# ziffy_board_v6.net
KiCad netlist of a schematic drawn in EAGLE
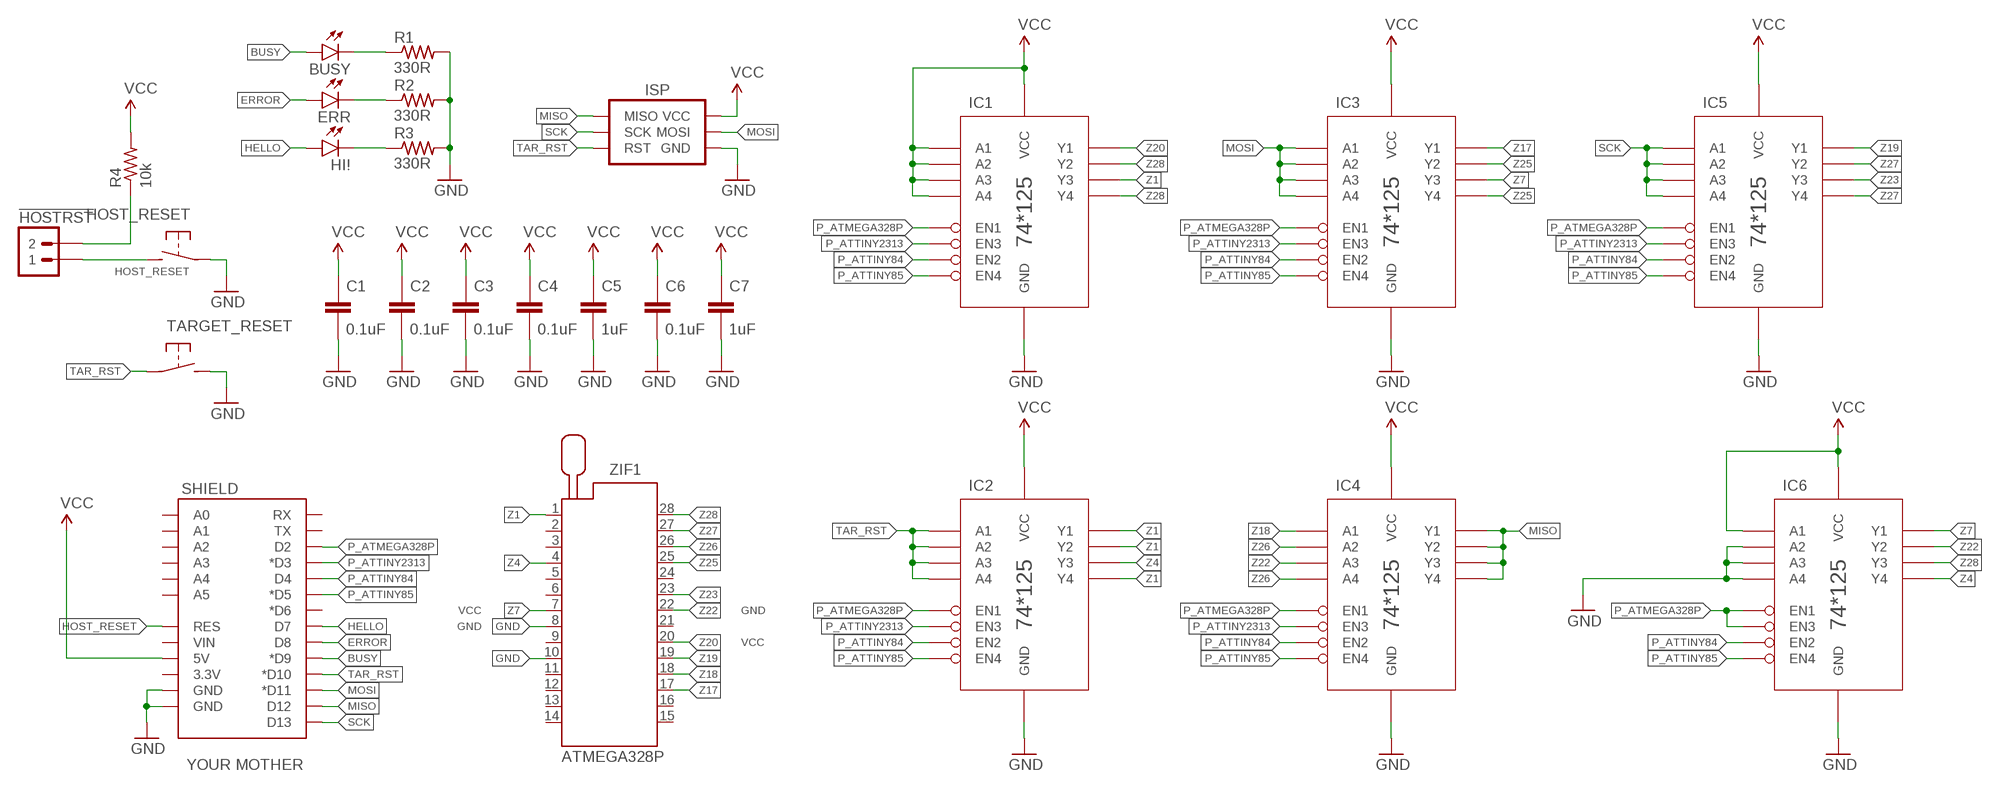
[diagram p0: schematic, sheet 1]

(export (version "E")
  (design (tool "Eeschema 10.0.6"))
  (components
    (comp (ref "!HOSTRST")
      (value "M02PTH")
      (footprint "eagle-import:1X02")
      (libsource (lib "eagle-import") (part "M02PTH"))
    )
    (comp (ref "BUSY")
      (value "YELLOW")
      (footprint "eagle-import:LED3MM")
      (libsource (lib "eagle-import") (part "LED3MM"))
    )
    (comp (ref "C1")
      (value "0.1uF")
      (footprint "eagle-import:C025-024X044")
      (libsource (lib "eagle-import") (part "CAPACITOR-CERAMIC025-024X044"))
    )
    (comp (ref "C2")
      (value "0.1uF")
      (footprint "eagle-import:C025-024X044")
      (libsource (lib "eagle-import") (part "CAPACITOR-CERAMIC025-024X044"))
    )
    (comp (ref "C3")
      (value "0.1uF")
      (footprint "eagle-import:C025-024X044")
      (libsource (lib "eagle-import") (part "CAPACITOR-CERAMIC025-024X044"))
    )
    (comp (ref "C4")
      (value "0.1uF")
      (footprint "eagle-import:C025-024X044")
      (libsource (lib "eagle-import") (part "CAPACITOR-CERAMIC025-024X044"))
    )
    (comp (ref "C5")
      (value "1uF")
      (footprint "eagle-import:C025-024X044")
      (libsource (lib "eagle-import") (part "CAPACITOR-CERAMIC025-024X044"))
    )
    (comp (ref "C6")
      (value "0.1uF")
      (footprint "eagle-import:C025-024X044")
      (libsource (lib "eagle-import") (part "CAPACITOR-CERAMIC025-024X044"))
    )
    (comp (ref "C7")
      (value "1uF")
      (footprint "eagle-import:C025-024X044")
      (libsource (lib "eagle-import") (part "CAPACITOR-CERAMIC025-024X044"))
    )
    (comp (ref "ERR")
      (value "RED")
      (footprint "eagle-import:LED3MM")
      (libsource (lib "eagle-import") (part "LED3MM"))
    )
    (comp (ref "HI!")
      (value "GREEN")
      (footprint "eagle-import:LED3MM")
      (libsource (lib "eagle-import") (part "LED3MM"))
    )
    (comp (ref "HOST_RESET")
      (value "SPST-NO-TACT6MM-PTH-SMALL-PADS")
      (footprint "eagle-import:DTS-6-SMALL-PADS")
      (libsource (lib "eagle-import") (part "SPST-NO-TACT6MM-PTH-SMALL-PADS"))
    )
    (comp (ref "IC1")
      (value "74HC125")
      (footprint "eagle-import:SO14")
      (libsource (lib "eagle-import") (part "74125SOIC14"))
    )
    (comp (ref "IC2")
      (value "74HC125")
      (footprint "eagle-import:SO14")
      (libsource (lib "eagle-import") (part "74125SOIC14"))
    )
    (comp (ref "IC3")
      (value "74HC125")
      (footprint "eagle-import:SO14")
      (libsource (lib "eagle-import") (part "74125SOIC14"))
    )
    (comp (ref "IC4")
      (value "74HC125")
      (footprint "eagle-import:SO14")
      (libsource (lib "eagle-import") (part "74125SOIC14"))
    )
    (comp (ref "IC5")
      (value "74HC125")
      (footprint "eagle-import:SO14")
      (libsource (lib "eagle-import") (part "74125SOIC14"))
    )
    (comp (ref "IC6")
      (value "74HC125")
      (footprint "eagle-import:SO14")
      (libsource (lib "eagle-import") (part "74125SOIC14"))
    )
    (comp (ref "ISP")
      (value "AVR_SPI_PRG_6PTH-SHROUD")
      (footprint "eagle-import:2X3-SHROUDED")
      (libsource (lib "eagle-import") (part "AVR_SPI_PRG_6PTH-SHROUD"))
    )
    (comp (ref "R1")
      (value "330R")
      (footprint "eagle-import:RESISTOR-AXIAL-PTH-5.08MM")
      (libsource (lib "eagle-import") (part "RESISTORPTH-AXIAL-5.08MM"))
    )
    (comp (ref "R2")
      (value "330R")
      (footprint "eagle-import:RESISTOR-AXIAL-PTH-5.08MM")
      (libsource (lib "eagle-import") (part "RESISTORPTH-AXIAL-5.08MM"))
    )
    (comp (ref "R3")
      (value "330R")
      (footprint "eagle-import:RESISTOR-AXIAL-PTH-5.08MM")
      (libsource (lib "eagle-import") (part "RESISTORPTH-AXIAL-5.08MM"))
    )
    (comp (ref "R4")
      (value "10k")
      (footprint "eagle-import:RESISTOR-AXIAL-PTH-5.08MM")
      (libsource (lib "eagle-import") (part "RESISTORPTH-AXIAL-5.08MM"))
    )
    (comp (ref "SHIELD")
      (value "YOUR MOTHER")
      (footprint "eagle-import:ARDUINO_SHIELD_NOOUTLINE_INSIDE_SMALLER")
      (libsource (lib "eagle-import") (part "ARDUINO_SHIELD_SMALLER"))
    )
    (comp (ref "TARGET_RESET")
      (value "SPST-NO-TACT6MM-PTH-SMALL-PADS")
      (footprint "eagle-import:DTS-6-SMALL-PADS")
      (libsource (lib "eagle-import") (part "SPST-NO-TACT6MM-PTH-SMALL-PADS"))
    )
    (comp (ref "ZIF1")
      (value "ATMEGA328P")
      (footprint "eagle-import:ZIF28")
      (libsource (lib "eagle-import") (part "ZIF28"))
    )
  )
  (nets
    (net (code "1") (name "BUSY") (class "Default")
      (node (ref "BUSY") (pin "A") (pinfunction "A_A") (pintype "passive"))
      (node (ref "SHIELD") (pin "D9") (pinfunction "*D9_D9") (pintype "bidirectional"))
    )
    (net (code "2") (name "ERROR") (class "Default")
      (node (ref "ERR") (pin "A") (pinfunction "A_A") (pintype "passive"))
      (node (ref "SHIELD") (pin "D8") (pinfunction "D8_D8") (pintype "bidirectional"))
    )
    (net (code "3") (name "GND") (class "Default")
      (node (ref "C1") (pin "2") (pinfunction "2_2") (pintype "passive"))
      (node (ref "C2") (pin "2") (pinfunction "2_2") (pintype "passive"))
      (node (ref "C3") (pin "2") (pinfunction "2_2") (pintype "passive"))
      (node (ref "C4") (pin "2") (pinfunction "2_2") (pintype "passive"))
      (node (ref "C5") (pin "2") (pinfunction "2_2") (pintype "passive"))
      (node (ref "C6") (pin "2") (pinfunction "2_2") (pintype "passive"))
      (node (ref "C7") (pin "2") (pinfunction "2_2") (pintype "passive"))
      (node (ref "HOST_RESET") (pin "1") (pinfunction "1_1") (pintype "passive"))
      (node (ref "HOST_RESET") (pin "2") (pinfunction "1_2") (pintype "passive"))
      (node (ref "IC1") (pin "7") (pinfunction "GND_7") (pintype "bidirectional"))
      (node (ref "IC2") (pin "7") (pinfunction "GND_7") (pintype "bidirectional"))
      (node (ref "IC3") (pin "7") (pinfunction "GND_7") (pintype "bidirectional"))
      (node (ref "IC4") (pin "7") (pinfunction "GND_7") (pintype "bidirectional"))
      (node (ref "IC5") (pin "7") (pinfunction "GND_7") (pintype "bidirectional"))
      (node (ref "IC6") (pin "12") (pinfunction "A4_12") (pintype "bidirectional"))
      (node (ref "IC6") (pin "5") (pinfunction "A2_5") (pintype "bidirectional"))
      (node (ref "IC6") (pin "7") (pinfunction "GND_7") (pintype "bidirectional"))
      (node (ref "IC6") (pin "9") (pinfunction "A3_9") (pintype "bidirectional"))
      (node (ref "ISP") (pin "6") (pinfunction "GND_6") (pintype "passive"))
      (node (ref "R1") (pin "P$2") (pinfunction "2_P$2") (pintype "passive"))
      (node (ref "R2") (pin "P$2") (pinfunction "2_P$2") (pintype "passive"))
      (node (ref "R3") (pin "P$2") (pinfunction "2_P$2") (pintype "passive"))
      (node (ref "SHIELD") (pin "GND@0") (pinfunction "GND_GND@0") (pintype "bidirectional"))
      (node (ref "SHIELD") (pin "GND@1") (pinfunction "GND_GND@1") (pintype "bidirectional"))
      (node (ref "TARGET_RESET") (pin "3") (pinfunction "2_3") (pintype "passive"))
      (node (ref "TARGET_RESET") (pin "4") (pinfunction "2_4") (pintype "passive"))
      (node (ref "ZIF1") (pin "10") (pinfunction "10_10") (pintype "passive"))
      (node (ref "ZIF1") (pin "8") (pinfunction "8_8") (pintype "passive"))
    )
    (net (code "4") (name "HELLO") (class "Default")
      (node (ref "HI!") (pin "A") (pinfunction "A_A") (pintype "passive"))
      (node (ref "SHIELD") (pin "D7") (pinfunction "D7_D7") (pintype "bidirectional"))
    )
    (net (code "5") (name "HOST_RESET") (class "Default")
      (node (ref "!HOSTRST") (pin "1") (pinfunction "1_1") (pintype "passive"))
      (node (ref "HOST_RESET") (pin "3") (pinfunction "2_3") (pintype "passive"))
      (node (ref "HOST_RESET") (pin "4") (pinfunction "2_4") (pintype "passive"))
      (node (ref "SHIELD") (pin "RES") (pinfunction "RES_RES") (pintype "bidirectional"))
    )
    (net (code "6") (name "MISO") (class "Default")
      (node (ref "IC4") (pin "11") (pinfunction "Y4_11") (pintype "bidirectional"))
      (node (ref "IC4") (pin "3") (pinfunction "Y1_3") (pintype "bidirectional"))
      (node (ref "IC4") (pin "6") (pinfunction "Y2_6") (pintype "bidirectional"))
      (node (ref "IC4") (pin "8") (pinfunction "Y3_8") (pintype "bidirectional"))
      (node (ref "ISP") (pin "1") (pinfunction "MISO_1") (pintype "passive"))
      (node (ref "SHIELD") (pin "D12") (pinfunction "D12_D12") (pintype "bidirectional"))
    )
    (net (code "7") (name "MOSI") (class "Default")
      (node (ref "IC3") (pin "12") (pinfunction "A4_12") (pintype "bidirectional"))
      (node (ref "IC3") (pin "2") (pinfunction "A1_2") (pintype "bidirectional"))
      (node (ref "IC3") (pin "5") (pinfunction "A2_5") (pintype "bidirectional"))
      (node (ref "IC3") (pin "9") (pinfunction "A3_9") (pintype "bidirectional"))
      (node (ref "ISP") (pin "4") (pinfunction "MOSI_4") (pintype "passive"))
      (node (ref "SHIELD") (pin "D11") (pinfunction "*D11_D11") (pintype "bidirectional"))
    )
    (net (code "8") (name "Net-(BUSY-C)") (class "Default")
      (node (ref "BUSY") (pin "K") (pinfunction "C_K") (pintype "passive"))
      (node (ref "R1") (pin "P$1") (pinfunction "1_P$1") (pintype "passive"))
    )
    (net (code "9") (name "Net-(ERR-C)") (class "Default")
      (node (ref "ERR") (pin "K") (pinfunction "C_K") (pintype "passive"))
      (node (ref "R2") (pin "P$1") (pinfunction "1_P$1") (pintype "passive"))
    )
    (net (code "10") (name "Net-(HI!-C)") (class "Default")
      (node (ref "HI!") (pin "K") (pinfunction "C_K") (pintype "passive"))
      (node (ref "R3") (pin "P$1") (pinfunction "1_P$1") (pintype "passive"))
    )
    (net (code "11") (name "Net-(R4-1)") (class "Default")
      (node (ref "!HOSTRST") (pin "2") (pinfunction "2_2") (pintype "passive"))
      (node (ref "R4") (pin "P$1") (pinfunction "1_P$1") (pintype "passive"))
    )
    (net (code "12") (name "P_ATMEGA328P") (class "Default")
      (node (ref "IC1") (pin "1") (pinfunction "EN1_1") (pintype "bidirectional"))
      (node (ref "IC2") (pin "1") (pinfunction "EN1_1") (pintype "bidirectional"))
      (node (ref "IC3") (pin "1") (pinfunction "EN1_1") (pintype "bidirectional"))
      (node (ref "IC4") (pin "1") (pinfunction "EN1_1") (pintype "bidirectional"))
      (node (ref "IC5") (pin "1") (pinfunction "EN1_1") (pintype "bidirectional"))
      (node (ref "IC6") (pin "1") (pinfunction "EN1_1") (pintype "bidirectional"))
      (node (ref "IC6") (pin "10") (pinfunction "EN3_10") (pintype "bidirectional"))
      (node (ref "SHIELD") (pin "D2") (pinfunction "D2_D2") (pintype "bidirectional"))
    )
    (net (code "13") (name "P_ATTINY84") (class "Default")
      (node (ref "IC1") (pin "4") (pinfunction "EN2_4") (pintype "bidirectional"))
      (node (ref "IC2") (pin "4") (pinfunction "EN2_4") (pintype "bidirectional"))
      (node (ref "IC3") (pin "4") (pinfunction "EN2_4") (pintype "bidirectional"))
      (node (ref "IC4") (pin "4") (pinfunction "EN2_4") (pintype "bidirectional"))
      (node (ref "IC5") (pin "4") (pinfunction "EN2_4") (pintype "bidirectional"))
      (node (ref "IC6") (pin "4") (pinfunction "EN2_4") (pintype "bidirectional"))
      (node (ref "SHIELD") (pin "D4") (pinfunction "D4_D4") (pintype "bidirectional"))
    )
    (net (code "14") (name "P_ATTINY85") (class "Default")
      (node (ref "IC1") (pin "13") (pinfunction "EN4_13") (pintype "bidirectional"))
      (node (ref "IC2") (pin "13") (pinfunction "EN4_13") (pintype "bidirectional"))
      (node (ref "IC3") (pin "13") (pinfunction "EN4_13") (pintype "bidirectional"))
      (node (ref "IC4") (pin "13") (pinfunction "EN4_13") (pintype "bidirectional"))
      (node (ref "IC5") (pin "13") (pinfunction "EN4_13") (pintype "bidirectional"))
      (node (ref "IC6") (pin "13") (pinfunction "EN4_13") (pintype "bidirectional"))
      (node (ref "SHIELD") (pin "D5") (pinfunction "*D5_D5") (pintype "bidirectional"))
    )
    (net (code "15") (name "P_ATTINY2313") (class "Default")
      (node (ref "IC1") (pin "10") (pinfunction "EN3_10") (pintype "bidirectional"))
      (node (ref "IC2") (pin "10") (pinfunction "EN3_10") (pintype "bidirectional"))
      (node (ref "IC3") (pin "10") (pinfunction "EN3_10") (pintype "bidirectional"))
      (node (ref "IC4") (pin "10") (pinfunction "EN3_10") (pintype "bidirectional"))
      (node (ref "IC5") (pin "10") (pinfunction "EN3_10") (pintype "bidirectional"))
      (node (ref "SHIELD") (pin "D3") (pinfunction "*D3_D3") (pintype "bidirectional"))
    )
    (net (code "16") (name "SCK") (class "Default")
      (node (ref "IC5") (pin "12") (pinfunction "A4_12") (pintype "bidirectional"))
      (node (ref "IC5") (pin "2") (pinfunction "A1_2") (pintype "bidirectional"))
      (node (ref "IC5") (pin "5") (pinfunction "A2_5") (pintype "bidirectional"))
      (node (ref "IC5") (pin "9") (pinfunction "A3_9") (pintype "bidirectional"))
      (node (ref "ISP") (pin "3") (pinfunction "SCK_3") (pintype "passive"))
      (node (ref "SHIELD") (pin "D13") (pinfunction "D13_D13") (pintype "bidirectional"))
    )
    (net (code "17") (name "TAR_RST") (class "Default")
      (node (ref "IC2") (pin "12") (pinfunction "A4_12") (pintype "bidirectional"))
      (node (ref "IC2") (pin "2") (pinfunction "A1_2") (pintype "bidirectional"))
      (node (ref "IC2") (pin "5") (pinfunction "A2_5") (pintype "bidirectional"))
      (node (ref "IC2") (pin "9") (pinfunction "A3_9") (pintype "bidirectional"))
      (node (ref "ISP") (pin "5") (pinfunction "RST_5") (pintype "passive"))
      (node (ref "SHIELD") (pin "D10") (pinfunction "*D10_D10") (pintype "bidirectional"))
      (node (ref "TARGET_RESET") (pin "1") (pinfunction "1_1") (pintype "passive"))
      (node (ref "TARGET_RESET") (pin "2") (pinfunction "1_2") (pintype "passive"))
    )
    (net (code "18") (name "VCC") (class "Default")
      (node (ref "C1") (pin "1") (pinfunction "1_1") (pintype "passive"))
      (node (ref "C2") (pin "1") (pinfunction "1_1") (pintype "passive"))
      (node (ref "C3") (pin "1") (pinfunction "1_1") (pintype "passive"))
      (node (ref "C4") (pin "1") (pinfunction "1_1") (pintype "passive"))
      (node (ref "C5") (pin "1") (pinfunction "1_1") (pintype "passive"))
      (node (ref "C6") (pin "1") (pinfunction "1_1") (pintype "passive"))
      (node (ref "C7") (pin "1") (pinfunction "1_1") (pintype "passive"))
      (node (ref "IC1") (pin "12") (pinfunction "A4_12") (pintype "bidirectional"))
      (node (ref "IC1") (pin "14") (pinfunction "VCC_14") (pintype "bidirectional"))
      (node (ref "IC1") (pin "2") (pinfunction "A1_2") (pintype "bidirectional"))
      (node (ref "IC1") (pin "5") (pinfunction "A2_5") (pintype "bidirectional"))
      (node (ref "IC1") (pin "9") (pinfunction "A3_9") (pintype "bidirectional"))
      (node (ref "IC2") (pin "14") (pinfunction "VCC_14") (pintype "bidirectional"))
      (node (ref "IC3") (pin "14") (pinfunction "VCC_14") (pintype "bidirectional"))
      (node (ref "IC4") (pin "14") (pinfunction "VCC_14") (pintype "bidirectional"))
      (node (ref "IC5") (pin "14") (pinfunction "VCC_14") (pintype "bidirectional"))
      (node (ref "IC6") (pin "14") (pinfunction "VCC_14") (pintype "bidirectional"))
      (node (ref "IC6") (pin "2") (pinfunction "A1_2") (pintype "bidirectional"))
      (node (ref "ISP") (pin "2") (pinfunction "VCC_2") (pintype "passive"))
      (node (ref "R4") (pin "P$2") (pinfunction "2_P$2") (pintype "passive"))
      (node (ref "SHIELD") (pin "5V") (pinfunction "5V_5V") (pintype "bidirectional"))
    )
    (net (code "19") (name "Z1") (class "Default")
      (node (ref "IC1") (pin "8") (pinfunction "Y3_8") (pintype "bidirectional"))
      (node (ref "IC2") (pin "11") (pinfunction "Y4_11") (pintype "bidirectional"))
      (node (ref "IC2") (pin "3") (pinfunction "Y1_3") (pintype "bidirectional"))
      (node (ref "IC2") (pin "6") (pinfunction "Y2_6") (pintype "bidirectional"))
      (node (ref "ZIF1") (pin "1") (pinfunction "1_1") (pintype "passive"))
    )
    (net (code "20") (name "Z4") (class "Default")
      (node (ref "IC2") (pin "8") (pinfunction "Y3_8") (pintype "bidirectional"))
      (node (ref "IC6") (pin "11") (pinfunction "Y4_11") (pintype "bidirectional"))
      (node (ref "ZIF1") (pin "4") (pinfunction "4_4") (pintype "passive"))
    )
    (net (code "21") (name "Z7") (class "Default")
      (node (ref "IC3") (pin "8") (pinfunction "Y3_8") (pintype "bidirectional"))
      (node (ref "IC6") (pin "3") (pinfunction "Y1_3") (pintype "bidirectional"))
      (node (ref "ZIF1") (pin "7") (pinfunction "7_7") (pintype "passive"))
    )
    (net (code "22") (name "Z17") (class "Default")
      (node (ref "IC3") (pin "3") (pinfunction "Y1_3") (pintype "bidirectional"))
      (node (ref "ZIF1") (pin "17") (pinfunction "17_17") (pintype "passive"))
    )
    (net (code "23") (name "Z18") (class "Default")
      (node (ref "IC4") (pin "2") (pinfunction "A1_2") (pintype "bidirectional"))
      (node (ref "ZIF1") (pin "18") (pinfunction "18_18") (pintype "passive"))
    )
    (net (code "24") (name "Z19") (class "Default")
      (node (ref "IC5") (pin "3") (pinfunction "Y1_3") (pintype "bidirectional"))
      (node (ref "ZIF1") (pin "19") (pinfunction "19_19") (pintype "passive"))
    )
    (net (code "25") (name "Z20") (class "Default")
      (node (ref "IC1") (pin "3") (pinfunction "Y1_3") (pintype "bidirectional"))
      (node (ref "ZIF1") (pin "20") (pinfunction "20_20") (pintype "passive"))
    )
    (net (code "26") (name "Z22") (class "Default")
      (node (ref "IC4") (pin "9") (pinfunction "A3_9") (pintype "bidirectional"))
      (node (ref "IC6") (pin "6") (pinfunction "Y2_6") (pintype "bidirectional"))
      (node (ref "ZIF1") (pin "22") (pinfunction "22_22") (pintype "passive"))
    )
    (net (code "27") (name "Z23") (class "Default")
      (node (ref "IC5") (pin "8") (pinfunction "Y3_8") (pintype "bidirectional"))
      (node (ref "ZIF1") (pin "23") (pinfunction "23_23") (pintype "passive"))
    )
    (net (code "28") (name "Z25") (class "Default")
      (node (ref "IC3") (pin "11") (pinfunction "Y4_11") (pintype "bidirectional"))
      (node (ref "IC3") (pin "6") (pinfunction "Y2_6") (pintype "bidirectional"))
      (node (ref "ZIF1") (pin "25") (pinfunction "25_25") (pintype "passive"))
    )
    (net (code "29") (name "Z26") (class "Default")
      (node (ref "IC4") (pin "12") (pinfunction "A4_12") (pintype "bidirectional"))
      (node (ref "IC4") (pin "5") (pinfunction "A2_5") (pintype "bidirectional"))
      (node (ref "ZIF1") (pin "26") (pinfunction "26_26") (pintype "passive"))
    )
    (net (code "30") (name "Z27") (class "Default")
      (node (ref "IC5") (pin "11") (pinfunction "Y4_11") (pintype "bidirectional"))
      (node (ref "IC5") (pin "6") (pinfunction "Y2_6") (pintype "bidirectional"))
      (node (ref "ZIF1") (pin "27") (pinfunction "27_27") (pintype "passive"))
    )
    (net (code "31") (name "Z28") (class "Default")
      (node (ref "IC1") (pin "11") (pinfunction "Y4_11") (pintype "bidirectional"))
      (node (ref "IC1") (pin "6") (pinfunction "Y2_6") (pintype "bidirectional"))
      (node (ref "IC6") (pin "8") (pinfunction "Y3_8") (pintype "bidirectional"))
      (node (ref "ZIF1") (pin "28") (pinfunction "28_28") (pintype "passive"))
    )
    (net (code "32") (name "unconnected-(SHIELD-*D6-PadD6)") (class "Default")
      (node (ref "SHIELD") (pin "D6") (pinfunction "*D6_D6") (pintype "bidirectional"))
    )
    (net (code "33") (name "unconnected-(SHIELD-Pad3.3V)") (class "Default")
      (node (ref "SHIELD") (pin "3.3V") (pinfunction "3.3V_3.3V") (pintype "bidirectional"))
    )
    (net (code "34") (name "unconnected-(SHIELD-PadA0)") (class "Default")
      (node (ref "SHIELD") (pin "A0") (pinfunction "A0_A0") (pintype "bidirectional"))
    )
    (net (code "35") (name "unconnected-(SHIELD-PadA1)") (class "Default")
      (node (ref "SHIELD") (pin "A1") (pinfunction "A1_A1") (pintype "bidirectional"))
    )
    (net (code "36") (name "unconnected-(SHIELD-PadA2)") (class "Default")
      (node (ref "SHIELD") (pin "A2") (pinfunction "A2_A2") (pintype "bidirectional"))
    )
    (net (code "37") (name "unconnected-(SHIELD-PadA3)") (class "Default")
      (node (ref "SHIELD") (pin "A3") (pinfunction "A3_A3") (pintype "bidirectional"))
    )
    (net (code "38") (name "unconnected-(SHIELD-PadA4)") (class "Default")
      (node (ref "SHIELD") (pin "A4") (pinfunction "A4_A4") (pintype "bidirectional"))
    )
    (net (code "39") (name "unconnected-(SHIELD-PadA5)") (class "Default")
      (node (ref "SHIELD") (pin "A5") (pinfunction "A5_A5") (pintype "bidirectional"))
    )
    (net (code "40") (name "unconnected-(SHIELD-PadRX)") (class "Default")
      (node (ref "SHIELD") (pin "RX") (pinfunction "RX_RX") (pintype "bidirectional"))
    )
    (net (code "41") (name "unconnected-(SHIELD-PadTX)") (class "Default")
      (node (ref "SHIELD") (pin "TX") (pinfunction "TX_TX") (pintype "bidirectional"))
    )
    (net (code "42") (name "unconnected-(SHIELD-PadVIN)") (class "Default")
      (node (ref "SHIELD") (pin "VIN") (pinfunction "VIN_VIN") (pintype "bidirectional"))
    )
    (net (code "43") (name "unconnected-(ZIF1-Pad2)") (class "Default")
      (node (ref "ZIF1") (pin "2") (pinfunction "2_2") (pintype "passive"))
    )
    (net (code "44") (name "unconnected-(ZIF1-Pad3)") (class "Default")
      (node (ref "ZIF1") (pin "3") (pinfunction "3_3") (pintype "passive"))
    )
    (net (code "45") (name "unconnected-(ZIF1-Pad5)") (class "Default")
      (node (ref "ZIF1") (pin "5") (pinfunction "5_5") (pintype "passive"))
    )
    (net (code "46") (name "unconnected-(ZIF1-Pad6)") (class "Default")
      (node (ref "ZIF1") (pin "6") (pinfunction "6_6") (pintype "passive"))
    )
    (net (code "47") (name "unconnected-(ZIF1-Pad9)") (class "Default")
      (node (ref "ZIF1") (pin "9") (pinfunction "9_9") (pintype "passive"))
    )
    (net (code "48") (name "unconnected-(ZIF1-Pad11)") (class "Default")
      (node (ref "ZIF1") (pin "11") (pinfunction "11_11") (pintype "passive"))
    )
    (net (code "49") (name "unconnected-(ZIF1-Pad12)") (class "Default")
      (node (ref "ZIF1") (pin "12") (pinfunction "12_12") (pintype "passive"))
    )
    (net (code "50") (name "unconnected-(ZIF1-Pad13)") (class "Default")
      (node (ref "ZIF1") (pin "13") (pinfunction "13_13") (pintype "passive"))
    )
    (net (code "51") (name "unconnected-(ZIF1-Pad14)") (class "Default")
      (node (ref "ZIF1") (pin "14") (pinfunction "14_14") (pintype "passive"))
    )
    (net (code "52") (name "unconnected-(ZIF1-Pad15)") (class "Default")
      (node (ref "ZIF1") (pin "15") (pinfunction "15_15") (pintype "passive"))
    )
    (net (code "53") (name "unconnected-(ZIF1-Pad16)") (class "Default")
      (node (ref "ZIF1") (pin "16") (pinfunction "16_16") (pintype "passive"))
    )
    (net (code "54") (name "unconnected-(ZIF1-Pad21)") (class "Default")
      (node (ref "ZIF1") (pin "21") (pinfunction "21_21") (pintype "passive"))
    )
    (net (code "55") (name "unconnected-(ZIF1-Pad24)") (class "Default")
      (node (ref "ZIF1") (pin "24") (pinfunction "24_24") (pintype "passive"))
    )
  )
)
